# esplashbpk.net
KiCad netlist of a schematic drawn in EAGLE
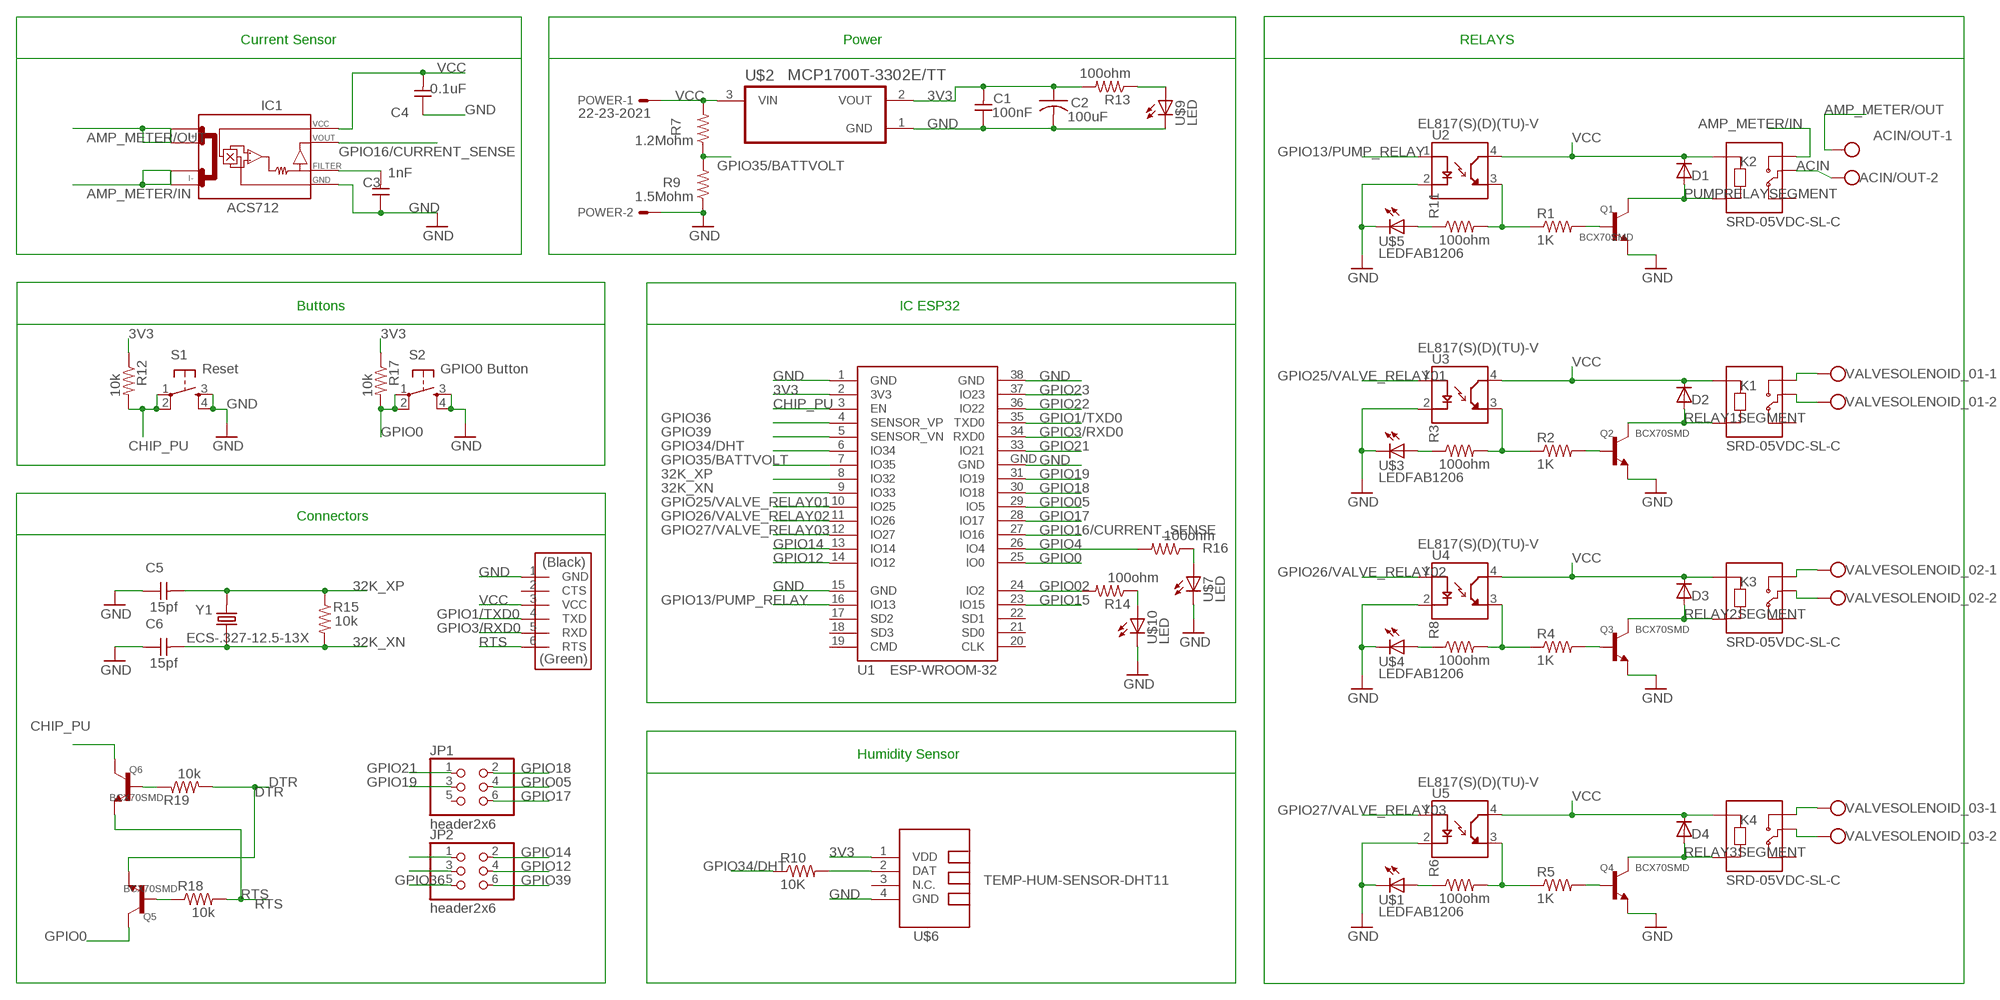
[diagram p0: schematic, sheet 1]

(export (version "E")
  (design (tool "Eeschema 10.0.6"))
  (components
    (comp (ref "ACIN/OUT")
      (value "W237-102")
      (footprint "eagle-import:W237-102")
      (fields (field (name "MPN") "237-102"))
      (libsource (lib "eagle-import") (part "W237-102"))
    )
    (comp (ref "C1")
      (value "100nF")
      (footprint "eagle-import:C1206FAB")
      (libsource (lib "eagle-import") (part "CAP-UNPOLARIZEDFAB"))
    )
    (comp (ref "C2")
      (value "100uF")
      (footprint "eagle-import:C1206FAB")
      (libsource (lib "eagle-import") (part "CAP-US1206FAB"))
    )
    (comp (ref "C3")
      (value "1nF")
      (footprint "eagle-import:C1206FAB")
      (libsource (lib "eagle-import") (part "CAP-UNPOLARIZEDFAB"))
    )
    (comp (ref "C4")
      (value "0.1uF")
      (footprint "eagle-import:C1206FAB")
      (libsource (lib "eagle-import") (part "CAP-UNPOLARIZEDFAB"))
    )
    (comp (ref "C5")
      (value "15pf")
      (footprint "eagle-import:C1206FAB")
      (libsource (lib "eagle-import") (part "CAP-UNPOLARIZEDFAB"))
    )
    (comp (ref "C6")
      (value "15pf")
      (footprint "eagle-import:C1206FAB")
      (libsource (lib "eagle-import") (part "CAP-UNPOLARIZEDFAB"))
    )
    (comp (ref "D1")
      (value "DIODESOD123")
      (footprint "eagle-import:SOD123")
      (libsource (lib "eagle-import") (part "DIODESOD123"))
    )
    (comp (ref "D2")
      (value "DIODESOD123")
      (footprint "eagle-import:SOD123")
      (libsource (lib "eagle-import") (part "DIODESOD123"))
    )
    (comp (ref "D3")
      (value "DIODESOD123")
      (footprint "eagle-import:SOD123")
      (libsource (lib "eagle-import") (part "DIODESOD123"))
    )
    (comp (ref "D4")
      (value "DIODESOD123")
      (footprint "eagle-import:SOD123")
      (libsource (lib "eagle-import") (part "DIODESOD123"))
    )
    (comp (ref "IC1")
      (value "ACS712")
      (footprint "eagle-import:SO08")
      (libsource (lib "eagle-import") (part "ACS712"))
    )
    (comp (ref "JP1")
      (value "header2x6")
      (footprint "eagle-import:2X03")
      (libsource (lib "eagle-import") (part "PINHD-2X3"))
    )
    (comp (ref "JP2")
      (value "header2x6")
      (footprint "eagle-import:2X03")
      (libsource (lib "eagle-import") (part "PINHD-2X3"))
    )
    (comp (ref "K1")
      (value "SRD-05VDC-SL-C")
      (footprint "eagle-import:RELAY_SRD-05VDC-SL-C")
      (fields (field (name "MF") "Songle Relay"))
      (libsource (lib "eagle-import") (part "SRD-05VDC-SL-C"))
    )
    (comp (ref "K2")
      (value "SRD-05VDC-SL-C")
      (footprint "eagle-import:RELAY_SRD-05VDC-SL-C")
      (fields (field (name "MF") "Songle Relay"))
      (libsource (lib "eagle-import") (part "SRD-05VDC-SL-C"))
    )
    (comp (ref "K3")
      (value "SRD-05VDC-SL-C")
      (footprint "eagle-import:RELAY_SRD-05VDC-SL-C")
      (fields (field (name "MF") "Songle Relay"))
      (libsource (lib "eagle-import") (part "SRD-05VDC-SL-C"))
    )
    (comp (ref "K4")
      (value "SRD-05VDC-SL-C")
      (footprint "eagle-import:RELAY_SRD-05VDC-SL-C")
      (fields (field (name "MF") "Songle Relay"))
      (libsource (lib "eagle-import") (part "SRD-05VDC-SL-C"))
    )
    (comp (ref "POWER")
      (value "22-23-2021")
      (footprint "eagle-import:22-23-2021")
      (fields (field (name "MF") "MOLEX"))
      (libsource (lib "eagle-import") (part "22-23-2021"))
    )
    (comp (ref "Q1")
      (value "BCX70SMD")
      (footprint "eagle-import:SOT23")
      (libsource (lib "eagle-import") (part "BCX70SMD"))
    )
    (comp (ref "Q2")
      (value "BCX70SMD")
      (footprint "eagle-import:SOT23")
      (libsource (lib "eagle-import") (part "BCX70SMD"))
    )
    (comp (ref "Q3")
      (value "BCX70SMD")
      (footprint "eagle-import:SOT23")
      (libsource (lib "eagle-import") (part "BCX70SMD"))
    )
    (comp (ref "Q4")
      (value "BCX70SMD")
      (footprint "eagle-import:SOT23")
      (libsource (lib "eagle-import") (part "BCX70SMD"))
    )
    (comp (ref "Q5")
      (value "BCX70SMD")
      (footprint "eagle-import:SOT23")
      (libsource (lib "eagle-import") (part "BCX70SMD"))
    )
    (comp (ref "Q6")
      (value "BCX70SMD")
      (footprint "eagle-import:SOT23")
      (libsource (lib "eagle-import") (part "BCX70SMD"))
    )
    (comp (ref "R1")
      (value "1K")
      (footprint "eagle-import:R1206FAB")
      (libsource (lib "eagle-import") (part "RES-US1206FAB"))
    )
    (comp (ref "R2")
      (value "1K")
      (footprint "eagle-import:R1206FAB")
      (libsource (lib "eagle-import") (part "RES-US1206FAB"))
    )
    (comp (ref "R3")
      (value "100ohm")
      (footprint "eagle-import:R1206FAB")
      (libsource (lib "eagle-import") (part "RES-US1206FAB"))
    )
    (comp (ref "R4")
      (value "1K")
      (footprint "eagle-import:R1206FAB")
      (libsource (lib "eagle-import") (part "RES-US1206FAB"))
    )
    (comp (ref "R5")
      (value "1K")
      (footprint "eagle-import:R1206FAB")
      (libsource (lib "eagle-import") (part "RES-US1206FAB"))
    )
    (comp (ref "R6")
      (value "100ohm")
      (footprint "eagle-import:R1206FAB")
      (libsource (lib "eagle-import") (part "RES-US1206FAB"))
    )
    (comp (ref "R7")
      (value "1.2Mohm")
      (footprint "eagle-import:R1206FAB")
      (libsource (lib "eagle-import") (part "RES-US1206FAB"))
    )
    (comp (ref "R8")
      (value "100ohm")
      (footprint "eagle-import:R1206FAB")
      (libsource (lib "eagle-import") (part "RES-US1206FAB"))
    )
    (comp (ref "R9")
      (value "1.5Mohm")
      (footprint "eagle-import:R1206FAB")
      (libsource (lib "eagle-import") (part "RES-US1206FAB"))
    )
    (comp (ref "R10")
      (value "10K")
      (footprint "eagle-import:R1206FAB")
      (libsource (lib "eagle-import") (part "RES-US1206FAB"))
    )
    (comp (ref "R11")
      (value "100ohm")
      (footprint "eagle-import:R1206FAB")
      (libsource (lib "eagle-import") (part "RES-US1206FAB"))
    )
    (comp (ref "R12")
      (value "10k")
      (footprint "eagle-import:R1206")
      (libsource (lib "eagle-import") (part "RES-US1206"))
    )
    (comp (ref "R13")
      (value "100ohm")
      (footprint "eagle-import:R1206")
      (libsource (lib "eagle-import") (part "RES-US1206"))
    )
    (comp (ref "R14")
      (value "100ohm")
      (footprint "eagle-import:R1206")
      (libsource (lib "eagle-import") (part "RES-US1206"))
    )
    (comp (ref "R15")
      (value "10k")
      (footprint "eagle-import:R1206")
      (libsource (lib "eagle-import") (part "RES-US1206"))
    )
    (comp (ref "R16")
      (value "100ohm")
      (footprint "eagle-import:R1206")
      (libsource (lib "eagle-import") (part "RES-US1206"))
    )
    (comp (ref "R17")
      (value "10k")
      (footprint "eagle-import:R1206")
      (libsource (lib "eagle-import") (part "RES-US1206"))
    )
    (comp (ref "R18")
      (value "10k")
      (footprint "eagle-import:R1206")
      (libsource (lib "eagle-import") (part "RES-US1206"))
    )
    (comp (ref "R19")
      (value "10k")
      (footprint "eagle-import:R1206")
      (libsource (lib "eagle-import") (part "RES-US1206"))
    )
    (comp (ref "RTS")
      (value "FTDI-SMD-HEADER")
      (footprint "eagle-import:1X06SMD")
      (libsource (lib "eagle-import") (part "FTDI-SMD-HEADER"))
    )
    (comp (ref "S1")
      (value "Reset")
      (footprint "eagle-import:6MM_SWITCH")
      (libsource (lib "eagle-import") (part "6MM_SWITCH6MM_SWITCH"))
    )
    (comp (ref "S2")
      (value "GPIO0 Button")
      (footprint "eagle-import:6MM_SWITCH")
      (libsource (lib "eagle-import") (part "6MM_SWITCH6MM_SWITCH"))
    )
    (comp (ref "U$1")
      (value "LEDFAB1206")
      (footprint "eagle-import:LED1206FAB")
      (libsource (lib "eagle-import") (part "LEDFAB1206"))
    )
    (comp (ref "U$2")
      (value "MCP1700T-3302E/TT")
      (footprint "eagle-import:SOT95P237X112-3N")
      (fields (field (name "MF") "Microchip Technology"))
      (libsource (lib "eagle-import") (part "MCP1700T-3302E/TT"))
    )
    (comp (ref "U$3")
      (value "LEDFAB1206")
      (footprint "eagle-import:LED1206FAB")
      (libsource (lib "eagle-import") (part "LEDFAB1206"))
    )
    (comp (ref "U$4")
      (value "LEDFAB1206")
      (footprint "eagle-import:LED1206FAB")
      (libsource (lib "eagle-import") (part "LEDFAB1206"))
    )
    (comp (ref "U$5")
      (value "LEDFAB1206")
      (footprint "eagle-import:LED1206FAB")
      (libsource (lib "eagle-import") (part "LEDFAB1206"))
    )
    (comp (ref "U$6")
      (value "TEMP-HUM-SENSOR-DHT11")
      (footprint "eagle-import:TEMP-HUM-SENSOR-DHT11")
      (libsource (lib "eagle-import") (part "TEMP-HUM-SENSOR-DHT11"))
    )
    (comp (ref "U$7")
      (value "LED")
      (footprint "eagle-import:LED1206")
      (libsource (lib "eagle-import") (part "LED"))
    )
    (comp (ref "U$9")
      (value "LED")
      (footprint "eagle-import:LED1206")
      (libsource (lib "eagle-import") (part "LED"))
    )
    (comp (ref "U$10")
      (value "LED")
      (footprint "eagle-import:LED1206")
      (libsource (lib "eagle-import") (part "LED"))
    )
    (comp (ref "U1")
      (value "ESP-WROOM-32")
      (footprint "eagle-import:ESP-WROOM-32")
      (libsource (lib "eagle-import") (part "ESP-WROOM-32"))
    )
    (comp (ref "U2")
      (value "EL817(S)(D)(TU)-V")
      (footprint "eagle-import:SOIC254P1030X460-4N")
      (fields (field (name "MF") "Everlight Electronics"))
      (libsource (lib "eagle-import") (part "EL817(S)(D)(TU)-V"))
    )
    (comp (ref "U3")
      (value "EL817(S)(D)(TU)-V")
      (footprint "eagle-import:SOIC254P1030X460-4N")
      (fields (field (name "MF") "Everlight Electronics"))
      (libsource (lib "eagle-import") (part "EL817(S)(D)(TU)-V"))
    )
    (comp (ref "U4")
      (value "EL817(S)(D)(TU)-V")
      (footprint "eagle-import:SOIC254P1030X460-4N")
      (fields (field (name "MF") "Everlight Electronics"))
      (libsource (lib "eagle-import") (part "EL817(S)(D)(TU)-V"))
    )
    (comp (ref "U5")
      (value "EL817(S)(D)(TU)-V")
      (footprint "eagle-import:SOIC254P1030X460-4N")
      (fields (field (name "MF") "Everlight Electronics"))
      (libsource (lib "eagle-import") (part "EL817(S)(D)(TU)-V"))
    )
    (comp (ref "VALVESOLENOID_01")
      (value "W237-102")
      (footprint "eagle-import:W237-102")
      (fields (field (name "MPN") "237-102"))
      (libsource (lib "eagle-import") (part "W237-102"))
    )
    (comp (ref "VALVESOLENOID_02")
      (value "W237-102")
      (footprint "eagle-import:W237-102")
      (fields (field (name "MPN") "237-102"))
      (libsource (lib "eagle-import") (part "W237-102"))
    )
    (comp (ref "VALVESOLENOID_03")
      (value "W237-102")
      (footprint "eagle-import:W237-102")
      (fields (field (name "MPN") "237-102"))
      (libsource (lib "eagle-import") (part "W237-102"))
    )
    (comp (ref "Y1")
      (value "ECS-.327-12.5-13X")
      (footprint "eagle-import:XTAL_ECS-.327-12.5-13X")
      (fields (field (name "MF") "ECS Inc."))
      (libsource (lib "eagle-import") (part "ECS-.327-12.5-13X"))
    )
  )
  (nets
    (net (code "1") (name "/3V3") (class "Default")
      (node (ref "C1") (pin "2") (pinfunction "2_2") (pintype "passive"))
      (node (ref "C2") (pin "1") (pinfunction "1_1") (pintype "passive"))
      (node (ref "R12") (pin "1") (pinfunction "1_1") (pintype "passive"))
      (node (ref "R13") (pin "2") (pinfunction "2_2") (pintype "passive"))
      (node (ref "R17") (pin "1") (pinfunction "1_1") (pintype "passive"))
      (node (ref "U$2") (pin "2") (pinfunction "VOUT_2") (pintype "output"))
      (node (ref "U$6") (pin "1") (pinfunction "VDD_1") (pintype "power_in"))
      (node (ref "U1") (pin "2") (pinfunction "3V3_2") (pintype "power_in"))
    )
    (net (code "2") (name "/32K_XN") (class "Default")
      (node (ref "C6") (pin "2") (pinfunction "2_2") (pintype "passive"))
      (node (ref "R15") (pin "2") (pinfunction "2_2") (pintype "passive"))
      (node (ref "U1") (pin "9") (pinfunction "IO33_9") (pintype "bidirectional"))
      (node (ref "Y1") (pin "1") (pinfunction "1_1") (pintype "passive"))
    )
    (net (code "3") (name "/32K_XP") (class "Default")
      (node (ref "C5") (pin "2") (pinfunction "2_2") (pintype "passive"))
      (node (ref "R15") (pin "1") (pinfunction "1_1") (pintype "passive"))
      (node (ref "U1") (pin "8") (pinfunction "IO32_8") (pintype "bidirectional"))
      (node (ref "Y1") (pin "2") (pinfunction "2_2") (pintype "passive"))
    )
    (net (code "4") (name "/ACIN") (class "Default")
      (node (ref "ACIN/OUT") (pin "2") (pinfunction "KL_2") (pintype "passive"))
      (node (ref "K2") (pin "COM") (pinfunction "COM_COM") (pintype "passive"))
    )
    (net (code "5") (name "/AMP_METER{slash}IN") (class "Default")
      (node (ref "IC1") (pin "3") (pinfunction "I-_0_3") (pintype "bidirectional"))
      (node (ref "IC1") (pin "4") (pinfunction "I-_1_4") (pintype "bidirectional"))
      (node (ref "K2") (pin "NO") (pinfunction "NO_NO") (pintype "passive"))
    )
    (net (code "6") (name "/AMP_METER{slash}OUT") (class "Default")
      (node (ref "ACIN/OUT") (pin "1") (pinfunction "KL_1") (pintype "passive"))
      (node (ref "IC1") (pin "1") (pinfunction "I+_0_1") (pintype "bidirectional"))
      (node (ref "IC1") (pin "2") (pinfunction "I+_1_2") (pintype "bidirectional"))
    )
    (net (code "7") (name "/CHIP_PU") (class "Default")
      (node (ref "Q6") (pin "3") (pinfunction "C_3") (pintype "passive"))
      (node (ref "R12") (pin "2") (pinfunction "2_2") (pintype "passive"))
      (node (ref "S1") (pin "1") (pinfunction "P_1") (pintype "passive"))
      (node (ref "S1") (pin "2") (pinfunction "P1_2") (pintype "passive"))
      (node (ref "U1") (pin "3") (pinfunction "EN_3") (pintype "input"))
    )
    (net (code "8") (name "/DTR") (class "Default")
      (node (ref "Q5") (pin "2") (pinfunction "E_2") (pintype "passive"))
      (node (ref "R19") (pin "2") (pinfunction "2_2") (pintype "passive"))
    )
    (net (code "9") (name "/GPIO0") (class "Default")
      (node (ref "Q5") (pin "3") (pinfunction "C_3") (pintype "passive"))
      (node (ref "R17") (pin "2") (pinfunction "2_2") (pintype "passive"))
      (node (ref "S2") (pin "1") (pinfunction "P_1") (pintype "passive"))
      (node (ref "S2") (pin "2") (pinfunction "P1_2") (pintype "passive"))
      (node (ref "U1") (pin "25") (pinfunction "IO0_25") (pintype "bidirectional"))
    )
    (net (code "10") (name "/GPIO1{slash}TXD0") (class "Default")
      (node (ref "RTS") (pin "4") (pinfunction "TXD_4") (pintype "bidirectional"))
      (node (ref "U1") (pin "35") (pinfunction "TXD0_35") (pintype "bidirectional"))
    )
    (net (code "11") (name "/GPIO02") (class "Default")
      (node (ref "R14") (pin "2") (pinfunction "2_2") (pintype "passive"))
      (node (ref "U1") (pin "24") (pinfunction "IO2_24") (pintype "bidirectional"))
    )
    (net (code "12") (name "/GPIO3{slash}RXD0") (class "Default")
      (node (ref "RTS") (pin "5") (pinfunction "RXD_5") (pintype "bidirectional"))
      (node (ref "U1") (pin "34") (pinfunction "RXD0_34") (pintype "bidirectional"))
    )
    (net (code "13") (name "/GPIO4") (class "Default")
      (node (ref "R16") (pin "2") (pinfunction "2_2") (pintype "passive"))
      (node (ref "U1") (pin "26") (pinfunction "IO4_26") (pintype "bidirectional"))
    )
    (net (code "14") (name "/GPIO05") (class "Default")
      (node (ref "JP1") (pin "4") (pinfunction "4_4") (pintype "passive"))
      (node (ref "U1") (pin "29") (pinfunction "IO5_29") (pintype "bidirectional"))
    )
    (net (code "15") (name "/GPIO12") (class "Default")
      (node (ref "JP2") (pin "4") (pinfunction "4_4") (pintype "passive"))
      (node (ref "U1") (pin "14") (pinfunction "IO12_14") (pintype "bidirectional"))
    )
    (net (code "16") (name "/GPIO13{slash}PUMP_RELAY") (class "Default")
      (node (ref "U1") (pin "16") (pinfunction "IO13_16") (pintype "bidirectional"))
      (node (ref "U2") (pin "1") (pinfunction "A_1") (pintype "passive"))
    )
    (net (code "17") (name "/GPIO14") (class "Default")
      (node (ref "JP2") (pin "2") (pinfunction "2_2") (pintype "passive"))
      (node (ref "U1") (pin "13") (pinfunction "IO14_13") (pintype "bidirectional"))
    )
    (net (code "18") (name "/GPIO15") (class "Default")
      (node (ref "U1") (pin "23") (pinfunction "IO15_23") (pintype "bidirectional"))
    )
    (net (code "19") (name "/GPIO16{slash}CURRENT_SENSE") (class "Default")
      (node (ref "IC1") (pin "7") (pinfunction "VOUT_7") (pintype "output"))
      (node (ref "U1") (pin "27") (pinfunction "IO16_27") (pintype "bidirectional"))
    )
    (net (code "20") (name "/GPIO17") (class "Default")
      (node (ref "JP1") (pin "6") (pinfunction "6_6") (pintype "passive"))
      (node (ref "U1") (pin "28") (pinfunction "IO17_28") (pintype "bidirectional"))
    )
    (net (code "21") (name "/GPIO18") (class "Default")
      (node (ref "JP1") (pin "2") (pinfunction "2_2") (pintype "passive"))
      (node (ref "U1") (pin "30") (pinfunction "IO18_30") (pintype "bidirectional"))
    )
    (net (code "22") (name "/GPIO19") (class "Default")
      (node (ref "JP1") (pin "3") (pinfunction "3_3") (pintype "passive"))
      (node (ref "U1") (pin "31") (pinfunction "IO19_31") (pintype "bidirectional"))
    )
    (net (code "23") (name "/GPIO21") (class "Default")
      (node (ref "JP1") (pin "1") (pinfunction "1_1") (pintype "passive"))
      (node (ref "U1") (pin "33") (pinfunction "IO21_33") (pintype "bidirectional"))
    )
    (net (code "24") (name "/GPIO22") (class "Default")
      (node (ref "U1") (pin "36") (pinfunction "IO22_36") (pintype "bidirectional"))
    )
    (net (code "25") (name "/GPIO23") (class "Default")
      (node (ref "U1") (pin "37") (pinfunction "IO23_37") (pintype "bidirectional"))
    )
    (net (code "26") (name "/GPIO25{slash}VALVE_RELAY01") (class "Default")
      (node (ref "U1") (pin "10") (pinfunction "IO25_10") (pintype "bidirectional"))
      (node (ref "U3") (pin "1") (pinfunction "A_1") (pintype "passive"))
    )
    (net (code "27") (name "/GPIO26{slash}VALVE_RELAY02") (class "Default")
      (node (ref "U1") (pin "11") (pinfunction "IO26_11") (pintype "bidirectional"))
      (node (ref "U4") (pin "1") (pinfunction "A_1") (pintype "passive"))
    )
    (net (code "28") (name "/GPIO27{slash}VALVE_RELAY03") (class "Default")
      (node (ref "U1") (pin "12") (pinfunction "IO27_12") (pintype "bidirectional"))
      (node (ref "U5") (pin "1") (pinfunction "A_1") (pintype "passive"))
    )
    (net (code "29") (name "/GPIO34{slash}DHT") (class "Default")
      (node (ref "R10") (pin "1") (pinfunction "1_1") (pintype "passive"))
      (node (ref "U1") (pin "6") (pinfunction "IO34_6") (pintype "bidirectional"))
    )
    (net (code "30") (name "/GPIO35{slash}BATTVOLT") (class "Default")
      (node (ref "R7") (pin "1") (pinfunction "1_1") (pintype "passive"))
      (node (ref "R9") (pin "2") (pinfunction "2_2") (pintype "passive"))
      (node (ref "U1") (pin "7") (pinfunction "IO35_7") (pintype "bidirectional"))
    )
    (net (code "31") (name "/GPIO36") (class "Default")
      (node (ref "JP2") (pin "5") (pinfunction "5_5") (pintype "passive"))
      (node (ref "U1") (pin "4") (pinfunction "SENSOR_VP_4") (pintype "bidirectional"))
    )
    (net (code "32") (name "/GPIO39") (class "Default")
      (node (ref "JP2") (pin "6") (pinfunction "6_6") (pintype "passive"))
      (node (ref "U1") (pin "5") (pinfunction "SENSOR_VN_5") (pintype "bidirectional"))
    )
    (net (code "33") (name "/PUMPRELAYSEGMENT") (class "Default")
      (node (ref "D1") (pin "ANODE") (pinfunction "A_ANODE") (pintype "passive"))
      (node (ref "K2") (pin "A2") (pinfunction "A2_A2") (pintype "passive"))
      (node (ref "Q1") (pin "3") (pinfunction "C_3") (pintype "passive"))
    )
    (net (code "34") (name "/RELAY1SEGMENT") (class "Default")
      (node (ref "D2") (pin "ANODE") (pinfunction "A_ANODE") (pintype "passive"))
      (node (ref "K1") (pin "A2") (pinfunction "A2_A2") (pintype "passive"))
      (node (ref "Q2") (pin "3") (pinfunction "C_3") (pintype "passive"))
    )
    (net (code "35") (name "/RELAY2SEGMENT") (class "Default")
      (node (ref "D3") (pin "ANODE") (pinfunction "A_ANODE") (pintype "passive"))
      (node (ref "K3") (pin "A2") (pinfunction "A2_A2") (pintype "passive"))
      (node (ref "Q3") (pin "3") (pinfunction "C_3") (pintype "passive"))
    )
    (net (code "36") (name "/RELAY3SEGMENT") (class "Default")
      (node (ref "D4") (pin "ANODE") (pinfunction "A_ANODE") (pintype "passive"))
      (node (ref "K4") (pin "A2") (pinfunction "A2_A2") (pintype "passive"))
      (node (ref "Q4") (pin "3") (pinfunction "C_3") (pintype "passive"))
    )
    (net (code "37") (name "/RTS") (class "Default")
      (node (ref "Q6") (pin "2") (pinfunction "E_2") (pintype "passive"))
      (node (ref "R18") (pin "2") (pinfunction "2_2") (pintype "passive"))
      (node (ref "RTS") (pin "6") (pinfunction "RTS_6") (pintype "bidirectional"))
    )
    (net (code "38") (name "/VCC") (class "Default")
      (node (ref "C4") (pin "2") (pinfunction "2_2") (pintype "passive"))
      (node (ref "D1") (pin "CATHODE") (pinfunction "C_CATHODE") (pintype "passive"))
      (node (ref "D2") (pin "CATHODE") (pinfunction "C_CATHODE") (pintype "passive"))
      (node (ref "D3") (pin "CATHODE") (pinfunction "C_CATHODE") (pintype "passive"))
      (node (ref "D4") (pin "CATHODE") (pinfunction "C_CATHODE") (pintype "passive"))
      (node (ref "IC1") (pin "8") (pinfunction "VCC_8") (pintype "power_in"))
      (node (ref "K1") (pin "A1") (pinfunction "A1_A1") (pintype "passive"))
      (node (ref "K2") (pin "A1") (pinfunction "A1_A1") (pintype "passive"))
      (node (ref "K3") (pin "A1") (pinfunction "A1_A1") (pintype "passive"))
      (node (ref "K4") (pin "A1") (pinfunction "A1_A1") (pintype "passive"))
      (node (ref "POWER") (pin "1") (pinfunction "S_1") (pintype "passive"))
      (node (ref "R7") (pin "2") (pinfunction "2_2") (pintype "passive"))
      (node (ref "RTS") (pin "3") (pinfunction "VCC_3") (pintype "bidirectional"))
      (node (ref "U$2") (pin "3") (pinfunction "VIN_3") (pintype "input"))
      (node (ref "U2") (pin "4") (pinfunction "CT_4") (pintype "passive"))
      (node (ref "U3") (pin "4") (pinfunction "CT_4") (pintype "passive"))
      (node (ref "U4") (pin "4") (pinfunction "CT_4") (pintype "passive"))
      (node (ref "U5") (pin "4") (pinfunction "CT_4") (pintype "passive"))
    )
    (net (code "39") (name "GND") (class "Default")
      (node (ref "C1") (pin "1") (pinfunction "1_1") (pintype "passive"))
      (node (ref "C2") (pin "2") (pinfunction "2_2") (pintype "passive"))
      (node (ref "C3") (pin "1") (pinfunction "1_1") (pintype "passive"))
      (node (ref "C4") (pin "1") (pinfunction "1_1") (pintype "passive"))
      (node (ref "C5") (pin "1") (pinfunction "1_1") (pintype "passive"))
      (node (ref "C6") (pin "1") (pinfunction "1_1") (pintype "passive"))
      (node (ref "IC1") (pin "5") (pinfunction "GND_5") (pintype "power_in"))
      (node (ref "POWER") (pin "2") (pinfunction "S_2") (pintype "passive"))
      (node (ref "Q1") (pin "2") (pinfunction "E_2") (pintype "passive"))
      (node (ref "Q2") (pin "2") (pinfunction "E_2") (pintype "passive"))
      (node (ref "Q3") (pin "2") (pinfunction "E_2") (pintype "passive"))
      (node (ref "Q4") (pin "2") (pinfunction "E_2") (pintype "passive"))
      (node (ref "R9") (pin "1") (pinfunction "1_1") (pintype "passive"))
      (node (ref "RTS") (pin "1") (pinfunction "GND_1") (pintype "bidirectional"))
      (node (ref "S1") (pin "3") (pinfunction "S_3") (pintype "passive"))
      (node (ref "S1") (pin "4") (pinfunction "S1_4") (pintype "passive"))
      (node (ref "S2") (pin "3") (pinfunction "S_3") (pintype "passive"))
      (node (ref "S2") (pin "4") (pinfunction "S1_4") (pintype "passive"))
      (node (ref "U$1") (pin "2") (pinfunction "C_2") (pintype "passive"))
      (node (ref "U$10") (pin "2") (pinfunction "C_2") (pintype "passive"))
      (node (ref "U$2") (pin "1") (pinfunction "GND_1") (pintype "power_in"))
      (node (ref "U$3") (pin "2") (pinfunction "C_2") (pintype "passive"))
      (node (ref "U$4") (pin "2") (pinfunction "C_2") (pintype "passive"))
      (node (ref "U$5") (pin "2") (pinfunction "C_2") (pintype "passive"))
      (node (ref "U$6") (pin "4") (pinfunction "GND_4") (pintype "power_in"))
      (node (ref "U$7") (pin "2") (pinfunction "C_2") (pintype "passive"))
      (node (ref "U$9") (pin "2") (pinfunction "C_2") (pintype "passive"))
      (node (ref "U1") (pin "1") (pinfunction "GND_1") (pintype "power_in"))
      (node (ref "U1") (pin "15") (pinfunction "GND_15") (pintype "power_in"))
      (node (ref "U1") (pin "38") (pinfunction "GND_38") (pintype "power_in"))
      (node (ref "U1") (pin "GND") (pinfunction "GND_GND") (pintype "power_in"))
      (node (ref "U2") (pin "2") (pinfunction "C_2") (pintype "passive"))
      (node (ref "U3") (pin "2") (pinfunction "C_2") (pintype "passive"))
      (node (ref "U4") (pin "2") (pinfunction "C_2") (pintype "passive"))
      (node (ref "U5") (pin "2") (pinfunction "C_2") (pintype "passive"))
    )
    (net (code "40") (name "Net-(IC1-FILTER)") (class "Default")
      (node (ref "C3") (pin "2") (pinfunction "2_2") (pintype "passive"))
      (node (ref "IC1") (pin "6") (pinfunction "FILTER_6") (pintype "bidirectional"))
    )
    (net (code "41") (name "Net-(Q1-B)") (class "Default")
      (node (ref "Q1") (pin "1") (pinfunction "B_1") (pintype "passive"))
      (node (ref "R1") (pin "2") (pinfunction "2_2") (pintype "passive"))
    )
    (net (code "42") (name "Net-(Q2-B)") (class "Default")
      (node (ref "Q2") (pin "1") (pinfunction "B_1") (pintype "passive"))
      (node (ref "R2") (pin "2") (pinfunction "2_2") (pintype "passive"))
    )
    (net (code "43") (name "Net-(Q3-B)") (class "Default")
      (node (ref "Q3") (pin "1") (pinfunction "B_1") (pintype "passive"))
      (node (ref "R4") (pin "2") (pinfunction "2_2") (pintype "passive"))
    )
    (net (code "44") (name "Net-(Q4-B)") (class "Default")
      (node (ref "Q4") (pin "1") (pinfunction "B_1") (pintype "passive"))
      (node (ref "R5") (pin "2") (pinfunction "2_2") (pintype "passive"))
    )
    (net (code "45") (name "Net-(Q5-B)") (class "Default")
      (node (ref "Q5") (pin "1") (pinfunction "B_1") (pintype "passive"))
      (node (ref "R18") (pin "1") (pinfunction "1_1") (pintype "passive"))
    )
    (net (code "46") (name "Net-(Q6-B)") (class "Default")
      (node (ref "Q6") (pin "1") (pinfunction "B_1") (pintype "passive"))
      (node (ref "R19") (pin "1") (pinfunction "1_1") (pintype "passive"))
    )
    (net (code "47") (name "Net-(U$1-A)") (class "Default")
      (node (ref "R6") (pin "1") (pinfunction "1_1") (pintype "passive"))
      (node (ref "U$1") (pin "1") (pinfunction "A_1") (pintype "passive"))
    )
    (net (code "48") (name "Net-(U$3-A)") (class "Default")
      (node (ref "R3") (pin "1") (pinfunction "1_1") (pintype "passive"))
      (node (ref "U$3") (pin "1") (pinfunction "A_1") (pintype "passive"))
    )
    (net (code "49") (name "Net-(U$4-A)") (class "Default")
      (node (ref "R8") (pin "1") (pinfunction "1_1") (pintype "passive"))
      (node (ref "U$4") (pin "1") (pinfunction "A_1") (pintype "passive"))
    )
    (net (code "50") (name "Net-(U$5-A)") (class "Default")
      (node (ref "R11") (pin "1") (pinfunction "1_1") (pintype "passive"))
      (node (ref "U$5") (pin "1") (pinfunction "A_1") (pintype "passive"))
    )
    (net (code "51") (name "Net-(U$6-DAT)") (class "Default")
      (node (ref "R10") (pin "2") (pinfunction "2_2") (pintype "passive"))
      (node (ref "U$6") (pin "2") (pinfunction "DAT_2") (pintype "bidirectional"))
    )
    (net (code "52") (name "Net-(U$7-A)") (class "Default")
      (node (ref "R16") (pin "1") (pinfunction "1_1") (pintype "passive"))
      (node (ref "U$7") (pin "1") (pinfunction "A_1") (pintype "passive"))
    )
    (net (code "53") (name "Net-(U$9-A)") (class "Default")
      (node (ref "R13") (pin "1") (pinfunction "1_1") (pintype "passive"))
      (node (ref "U$9") (pin "1") (pinfunction "A_1") (pintype "passive"))
    )
    (net (code "54") (name "Net-(U$10-A)") (class "Default")
      (node (ref "R14") (pin "1") (pinfunction "1_1") (pintype "passive"))
      (node (ref "U$10") (pin "1") (pinfunction "A_1") (pintype "passive"))
    )
    (net (code "55") (name "Net-(U2-ET)") (class "Default")
      (node (ref "R1") (pin "1") (pinfunction "1_1") (pintype "passive"))
      (node (ref "R11") (pin "2") (pinfunction "2_2") (pintype "passive"))
      (node (ref "U2") (pin "3") (pinfunction "ET_3") (pintype "passive"))
    )
    (net (code "56") (name "Net-(U3-ET)") (class "Default")
      (node (ref "R2") (pin "1") (pinfunction "1_1") (pintype "passive"))
      (node (ref "R3") (pin "2") (pinfunction "2_2") (pintype "passive"))
      (node (ref "U3") (pin "3") (pinfunction "ET_3") (pintype "passive"))
    )
    (net (code "57") (name "Net-(U4-ET)") (class "Default")
      (node (ref "R4") (pin "1") (pinfunction "1_1") (pintype "passive"))
      (node (ref "R8") (pin "2") (pinfunction "2_2") (pintype "passive"))
      (node (ref "U4") (pin "3") (pinfunction "ET_3") (pintype "passive"))
    )
    (net (code "58") (name "Net-(U5-ET)") (class "Default")
      (node (ref "R5") (pin "1") (pinfunction "1_1") (pintype "passive"))
      (node (ref "R6") (pin "2") (pinfunction "2_2") (pintype "passive"))
      (node (ref "U5") (pin "3") (pinfunction "ET_3") (pintype "passive"))
    )
    (net (code "59") (name "Net-(VALVESOLENOID_01A-KL)") (class "Default")
      (node (ref "K1") (pin "NO") (pinfunction "NO_NO") (pintype "passive"))
      (node (ref "VALVESOLENOID_01") (pin "1") (pinfunction "KL_1") (pintype "passive"))
    )
    (net (code "60") (name "Net-(VALVESOLENOID_01B-KL)") (class "Default")
      (node (ref "K1") (pin "COM") (pinfunction "COM_COM") (pintype "passive"))
      (node (ref "VALVESOLENOID_01") (pin "2") (pinfunction "KL_2") (pintype "passive"))
    )
    (net (code "61") (name "Net-(VALVESOLENOID_02A-KL)") (class "Default")
      (node (ref "K3") (pin "NO") (pinfunction "NO_NO") (pintype "passive"))
      (node (ref "VALVESOLENOID_02") (pin "1") (pinfunction "KL_1") (pintype "passive"))
    )
    (net (code "62") (name "Net-(VALVESOLENOID_02B-KL)") (class "Default")
      (node (ref "K3") (pin "COM") (pinfunction "COM_COM") (pintype "passive"))
      (node (ref "VALVESOLENOID_02") (pin "2") (pinfunction "KL_2") (pintype "passive"))
    )
    (net (code "63") (name "Net-(VALVESOLENOID_03A-KL)") (class "Default")
      (node (ref "K4") (pin "NO") (pinfunction "NO_NO") (pintype "passive"))
      (node (ref "VALVESOLENOID_03") (pin "1") (pinfunction "KL_1") (pintype "passive"))
    )
    (net (code "64") (name "Net-(VALVESOLENOID_03B-KL)") (class "Default")
      (node (ref "K4") (pin "COM") (pinfunction "COM_COM") (pintype "passive"))
      (node (ref "VALVESOLENOID_03") (pin "2") (pinfunction "KL_2") (pintype "passive"))
    )
    (net (code "65") (name "unconnected-(JP1-Pad5)") (class "Default")
      (node (ref "JP1") (pin "5") (pinfunction "5_5") (pintype "passive"))
    )
    (net (code "66") (name "unconnected-(JP2-Pad1)") (class "Default")
      (node (ref "JP2") (pin "1") (pinfunction "1_1") (pintype "passive"))
    )
    (net (code "67") (name "unconnected-(JP2-Pad3)") (class "Default")
      (node (ref "JP2") (pin "3") (pinfunction "3_3") (pintype "passive"))
    )
    (net (code "68") (name "unconnected-(K1-PadNC)") (class "Default")
      (node (ref "K1") (pin "NC") (pinfunction "NC_NC") (pintype "passive"))
    )
    (net (code "69") (name "unconnected-(K2-PadNC)") (class "Default")
      (node (ref "K2") (pin "NC") (pinfunction "NC_NC") (pintype "passive"))
    )
    (net (code "70") (name "unconnected-(K3-PadNC)") (class "Default")
      (node (ref "K3") (pin "NC") (pinfunction "NC_NC") (pintype "passive"))
    )
    (net (code "71") (name "unconnected-(K4-PadNC)") (class "Default")
      (node (ref "K4") (pin "NC") (pinfunction "NC_NC") (pintype "passive"))
    )
    (net (code "72") (name "unconnected-(RTS-CTS-Pad2)") (class "Default")
      (node (ref "RTS") (pin "2") (pinfunction "CTS_2") (pintype "bidirectional"))
    )
    (net (code "73") (name "unconnected-(U$6-N.C.-Pad3)") (class "Default")
      (node (ref "U$6") (pin "3") (pinfunction "N.C._3") (pintype "passive"))
    )
    (net (code "74") (name "unconnected-(U1-CLK-Pad20)") (class "Default")
      (node (ref "U1") (pin "20") (pinfunction "CLK_20") (pintype "bidirectional"))
    )
    (net (code "75") (name "unconnected-(U1-CMD-Pad19)") (class "Default")
      (node (ref "U1") (pin "19") (pinfunction "CMD_19") (pintype "bidirectional"))
    )
    (net (code "76") (name "unconnected-(U1-SD0-Pad21)") (class "Default")
      (node (ref "U1") (pin "21") (pinfunction "SD0_21") (pintype "bidirectional"))
    )
    (net (code "77") (name "unconnected-(U1-SD1-Pad22)") (class "Default")
      (node (ref "U1") (pin "22") (pinfunction "SD1_22") (pintype "bidirectional"))
    )
    (net (code "78") (name "unconnected-(U1-SD2-Pad17)") (class "Default")
      (node (ref "U1") (pin "17") (pinfunction "SD2_17") (pintype "bidirectional"))
    )
    (net (code "79") (name "unconnected-(U1-SD3-Pad18)") (class "Default")
      (node (ref "U1") (pin "18") (pinfunction "SD3_18") (pintype "bidirectional"))
    )
  )
)
